# electric_schematic.net
KiCad netlist of a schematic drawn in EAGLE
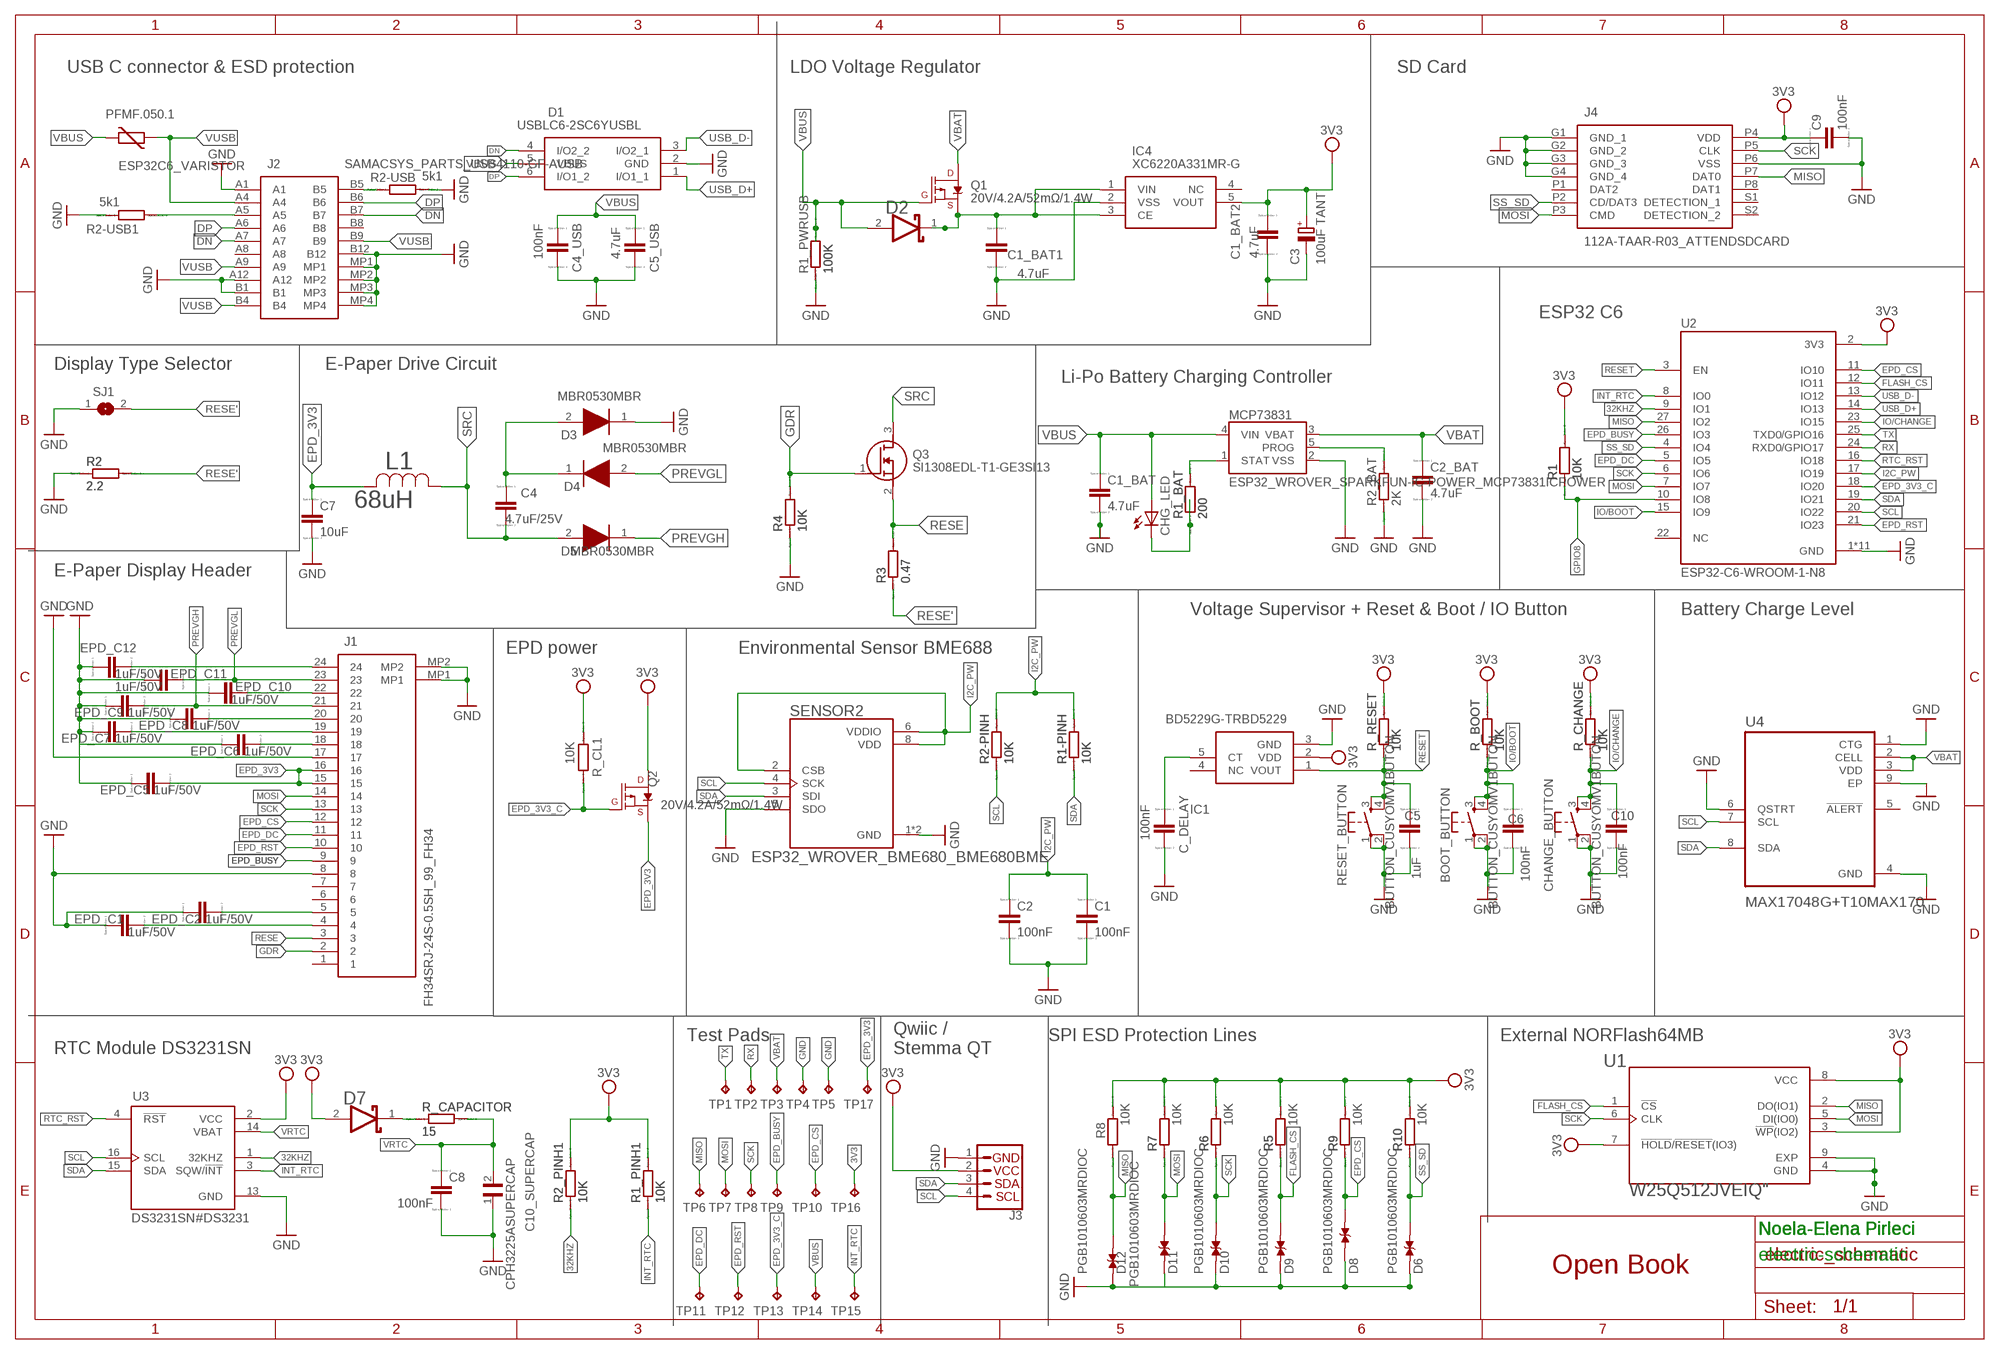
[diagram p0: schematic, sheet 1]

(export (version "E")
  (design (tool "Eeschema 10.0.6"))
  (components
    (comp (ref "BOOT_BUTTON")
      (value "BUTTON_CUSYOMV1BUTON")
      (footprint "eagle-import:MYBUTTON")
      (libsource (lib "eagle-import") (part "BUTTON_CUSYOMV1BUTON"))
    )
    (comp (ref "C1")
      (value "100nF")
      (footprint "eagle-import:ESP32_WROVER_EAGLE-LTSPICE_C0402")
      (libsource (lib "eagle-import") (part "EAGLE-LTSPICE_C"))
    )
    (comp (ref "C1_BAT")
      (value "4.7uF")
      (footprint "eagle-import:ESP32_WROVER_EAGLE-LTSPICE_C0402")
      (libsource (lib "eagle-import") (part "ESP32_WROVER_EAGLE-LTSPICE_C"))
    )
    (comp (ref "C1_BAT1")
      (value "4.7uF")
      (footprint "eagle-import:ESP32_WROVER_EAGLE-LTSPICE_C0402")
      (libsource (lib "eagle-import") (part "ESP32_WROVER_EAGLE-LTSPICE_C"))
    )
    (comp (ref "C1_BAT2")
      (value "4.7uF")
      (footprint "eagle-import:ESP32_WROVER_EAGLE-LTSPICE_C0402")
      (libsource (lib "eagle-import") (part "ESP32_WROVER_EAGLE-LTSPICE_C"))
    )
    (comp (ref "C2")
      (value "100nF")
      (footprint "eagle-import:ESP32_WROVER_EAGLE-LTSPICE_C0402")
      (libsource (lib "eagle-import") (part "ESP32_WROVER_EAGLE-LTSPICE_C"))
    )
    (comp (ref "C2_BAT")
      (value "4.7uF")
      (footprint "eagle-import:ESP32_WROVER_EAGLE-LTSPICE_C0402")
      (libsource (lib "eagle-import") (part "ESP32_WROVER_EAGLE-LTSPICE_C"))
    )
    (comp (ref "C3")
      (value "100uF TANT")
      (footprint "eagle-import:RCL_CT3528")
      (libsource (lib "eagle-import") (part "RCL_CPOL-EU"))
    )
    (comp (ref "C4")
      (value "4.7uF/25V")
      (footprint "eagle-import:ESP32_WROVER_EAGLE-LTSPICE_C0402")
      (libsource (lib "eagle-import") (part "EAGLE-LTSPICE_C"))
    )
    (comp (ref "C4_USB")
      (value "100nF")
      (footprint "eagle-import:ESP32_WROVER_EAGLE-LTSPICE_C0402")
      (libsource (lib "eagle-import") (part "EAGLE-LTSPICE_C"))
    )
    (comp (ref "C5")
      (value "1uF")
      (footprint "eagle-import:ESP32_WROVER_EAGLE-LTSPICE_C0402")
      (libsource (lib "eagle-import") (part "ESP32_WROVER_EAGLE-LTSPICE_C"))
    )
    (comp (ref "C5_USB")
      (value "4.7uF")
      (footprint "eagle-import:ESP32_WROVER_EAGLE-LTSPICE_C0402")
      (libsource (lib "eagle-import") (part "EAGLE-LTSPICE_C"))
    )
    (comp (ref "C6")
      (value "100nF")
      (footprint "eagle-import:ESP32_WROVER_EAGLE-LTSPICE_C0402")
      (libsource (lib "eagle-import") (part "ESP32_WROVER_EAGLE-LTSPICE_C"))
    )
    (comp (ref "C7")
      (value "10uF")
      (footprint "eagle-import:ESP32_WROVER_EAGLE-LTSPICE_C0402")
      (libsource (lib "eagle-import") (part "ESP32_WROVER_EAGLE-LTSPICE_C"))
    )
    (comp (ref "C8")
      (value "100nF")
      (footprint "eagle-import:ESP32_WROVER_EAGLE-LTSPICE_C0402")
      (libsource (lib "eagle-import") (part "ESP32_WROVER_EAGLE-LTSPICE_C"))
    )
    (comp (ref "C9")
      (value "100nF")
      (footprint "eagle-import:ESP32_WROVER_EAGLE-LTSPICE_C0402")
      (libsource (lib "eagle-import") (part "EAGLE-LTSPICE_C"))
    )
    (comp (ref "C10")
      (value "100nF")
      (footprint "eagle-import:ESP32_WROVER_EAGLE-LTSPICE_C0402")
      (libsource (lib "eagle-import") (part "ESP32_WROVER_EAGLE-LTSPICE_C"))
    )
    (comp (ref "C10_SUPERCAP")
      (value "CPH3225ASUPERCAP")
      (footprint "eagle-import:CAPCP3225X100N")
      (libsource (lib "eagle-import") (part "CPH3225ASUPERCAP"))
    )
    (comp (ref "CHANGE_BUTTON")
      (value "BUTTON_CUSYOMV1BUTON")
      (footprint "eagle-import:MYBUTTON")
      (libsource (lib "eagle-import") (part "BUTTON_CUSYOMV1BUTON"))
    )
    (comp (ref "CHG_LED")
      (value "ADAFRUIT_LED")
      (footprint "eagle-import:ADAFRUIT_CHIP-LED0603")
      (libsource (lib "eagle-import") (part "ADAFRUIT_LED"))
    )
    (comp (ref "C_DELAY")
      (value "100nF")
      (footprint "eagle-import:ESP32_WROVER_EAGLE-LTSPICE_C0402")
      (libsource (lib "eagle-import") (part "EAGLE-LTSPICE_C"))
    )
    (comp (ref "D1")
      (value "USBLC6-2SC6YUSBL")
      (footprint "eagle-import:SOT95P280X145-6N")
      (libsource (lib "eagle-import") (part "USBLC6-2SC6YUSBL"))
    )
    (comp (ref "D2")
      (value "ESP32_WROVER_AVX---SD0805S020S1R0_AVX_SD0805S020S1R0_0_0")
      (footprint "eagle-import:ESP32_WROVER_AVX---SD0805S020S1R0_AVX_SD0805S020S1R0_0")
      (libsource (lib "eagle-import") (part "ESP32_WROVER_AVX---SD0805S020S1R0_AVX_SD0805S020S1R0_0_0"))
    )
    (comp (ref "D3")
      (value "MBR0530MBR")
      (footprint "eagle-import:SOD3716X135N")
      (libsource (lib "eagle-import") (part "MBR0530MBR"))
    )
    (comp (ref "D4")
      (value "MBR0530MBR")
      (footprint "eagle-import:SOD3716X135N")
      (libsource (lib "eagle-import") (part "MBR0530MBR"))
    )
    (comp (ref "D5")
      (value "MBR0530MBR")
      (footprint "eagle-import:SOD3716X135N")
      (libsource (lib "eagle-import") (part "MBR0530MBR"))
    )
    (comp (ref "D6")
      (value "PGB1010603MRDIOC")
      (footprint "eagle-import:DIOC1608X36N")
      (libsource (lib "eagle-import") (part "PGB1010603MRDIOC"))
    )
    (comp (ref "D7")
      (value "ESP32_WROVER_AVX---SD0805S020S1R0_AVX_SD0805S020S1R0_0_0")
      (footprint "eagle-import:ESP32_WROVER_AVX---SD0805S020S1R0_AVX_SD0805S020S1R0_0")
      (libsource (lib "eagle-import") (part "ESP32_WROVER_AVX---SD0805S020S1R0_AVX_SD0805S020S1R0_0_0"))
    )
    (comp (ref "D8")
      (value "PGB1010603MRDIOC")
      (footprint "eagle-import:DIOC1608X36N")
      (libsource (lib "eagle-import") (part "PGB1010603MRDIOC"))
    )
    (comp (ref "D9")
      (value "PGB1010603MRDIOC")
      (footprint "eagle-import:DIOC1608X36N")
      (libsource (lib "eagle-import") (part "PGB1010603MRDIOC"))
    )
    (comp (ref "D10")
      (value "PGB1010603MRDIOC")
      (footprint "eagle-import:DIOC1608X36N")
      (libsource (lib "eagle-import") (part "PGB1010603MRDIOC"))
    )
    (comp (ref "D11")
      (value "PGB1010603MRDIOC")
      (footprint "eagle-import:DIOC1608X36N")
      (libsource (lib "eagle-import") (part "PGB1010603MRDIOC"))
    )
    (comp (ref "D12")
      (value "PGB1010603MRDIOC")
      (footprint "eagle-import:DIOC1608X36N")
      (libsource (lib "eagle-import") (part "PGB1010603MRDIOC"))
    )
    (comp (ref "EPD_C1")
      (value "1uF/50V")
      (footprint "eagle-import:ESP32_WROVER_EAGLE-LTSPICE_C0402")
      (libsource (lib "eagle-import") (part "ESP32_WROVER_EAGLE-LTSPICE_C"))
    )
    (comp (ref "EPD_C2")
      (value "1uF/50V")
      (footprint "eagle-import:ESP32_WROVER_EAGLE-LTSPICE_C0402")
      (libsource (lib "eagle-import") (part "ESP32_WROVER_EAGLE-LTSPICE_C"))
    )
    (comp (ref "EPD_C5")
      (value "1uF/50V")
      (footprint "eagle-import:ESP32_WROVER_EAGLE-LTSPICE_C0402")
      (libsource (lib "eagle-import") (part "ESP32_WROVER_EAGLE-LTSPICE_C"))
    )
    (comp (ref "EPD_C6")
      (value "1uF/50V")
      (footprint "eagle-import:ESP32_WROVER_EAGLE-LTSPICE_C0402")
      (libsource (lib "eagle-import") (part "ESP32_WROVER_EAGLE-LTSPICE_C"))
    )
    (comp (ref "EPD_C7")
      (value "1uF/50V")
      (footprint "eagle-import:ESP32_WROVER_EAGLE-LTSPICE_C0402")
      (libsource (lib "eagle-import") (part "ESP32_WROVER_EAGLE-LTSPICE_C"))
    )
    (comp (ref "EPD_C8")
      (value "1uF/50V")
      (footprint "eagle-import:ESP32_WROVER_EAGLE-LTSPICE_C0402")
      (libsource (lib "eagle-import") (part "ESP32_WROVER_EAGLE-LTSPICE_C"))
    )
    (comp (ref "EPD_C9")
      (value "1uF/50V")
      (footprint "eagle-import:ESP32_WROVER_EAGLE-LTSPICE_C0402")
      (libsource (lib "eagle-import") (part "ESP32_WROVER_EAGLE-LTSPICE_C"))
    )
    (comp (ref "EPD_C10")
      (value "1uF/50V")
      (footprint "eagle-import:ESP32_WROVER_EAGLE-LTSPICE_C0402")
      (libsource (lib "eagle-import") (part "ESP32_WROVER_EAGLE-LTSPICE_C"))
    )
    (comp (ref "EPD_C11")
      (value "1uF/50V")
      (footprint "eagle-import:ESP32_WROVER_EAGLE-LTSPICE_C0402")
      (libsource (lib "eagle-import") (part "ESP32_WROVER_EAGLE-LTSPICE_C"))
    )
    (comp (ref "EPD_C12")
      (value "1uF/50V")
      (footprint "eagle-import:ESP32_WROVER_EAGLE-LTSPICE_C0402")
      (libsource (lib "eagle-import") (part "ESP32_WROVER_EAGLE-LTSPICE_C"))
    )
    (comp (ref "IC1")
      (value "BD5229G-TRBD5229")
      (footprint "eagle-import:SOT95P280X125-5N")
      (libsource (lib "eagle-import") (part "BD5229G-TRBD5229"))
    )
    (comp (ref "IC4")
      (value "XC6220A331MR-G")
      (footprint "eagle-import:SOT95P280X120-5N")
      (fields (field (name "MOUSER_PART_NUMBER") "865-XC6220A331MR-G"))
      (libsource (lib "eagle-import") (part "XC6220A331MR-G"))
    )
    (comp (ref "J1")
      (value "FH34SRJ-24S-0.5SH_99_FH34")
      (footprint "eagle-import:FH34SRJ24S05SH99")
      (libsource (lib "eagle-import") (part "FH34SRJ-24S-0.5SH_99_FH34"))
    )
    (comp (ref "J2")
      (value "SAMACSYS_PARTS_USB4110-GF-AUSB")
      (footprint "eagle-import:SAMACSYS_PARTS_USB4110GFA")
      (libsource (lib "eagle-import") (part "SAMACSYS_PARTS_USB4110-GF-AUSB"))
    )
    (comp (ref "J3")
      (value "QWIIC_RIGHT_ANGLE")
      (footprint "eagle-import:JST04_1MM_RA")
      (libsource (lib "eagle-import") (part "QWIIC_CONNECTOR"))
    )
    (comp (ref "J4")
      (value "112A-TAAR-R03_ATTENDSDCARD")
      (footprint "eagle-import:112ATAARR03ATTEND")
      (libsource (lib "eagle-import") (part "112A-TAAR-R03_ATTENDSDCARD"))
    )
    (comp (ref "L1")
      (value "68uH")
      (footprint "eagle-import:IND_4828-WE-TPC_WRE")
      (libsource (lib "eagle-import") (part "744043680"))
    )
    (comp (ref "MCP73831")
      (value "ESP32_WROVER_SPARKFUN-IC-POWER_MCP73831ICPOWER")
      (footprint "eagle-import:ESP32_WROVER_SPARKFUN-IC-POWER_SOT23-5")
      (libsource (lib "eagle-import") (part "ESP32_WROVER_SPARKFUN-IC-POWER_MCP73831ICPOWER"))
    )
    (comp (ref "PFMF.050.1")
      (value "ESP32C6_VARISTOR")
      (footprint "eagle-import:ESP32C6_VARISTOR_CT_CN1812")
      (libsource (lib "eagle-import") (part "ESP32C6_VARISTOR"))
    )
    (comp (ref "Q1")
      (value "20V/4.2A/52mΩ/1.4W")
      (footprint "eagle-import:ESP32_WROVER_SPARKFUN-DISCRETESEMI_SOT23-3")
      (libsource (lib "eagle-import") (part "ESP32_WROVER_SPARKFUN-DISCRETESEMI_MOSFET_PCH"))
    )
    (comp (ref "Q2")
      (value "20V/4.2A/52mΩ/1.4W")
      (footprint "eagle-import:ESP32_WROVER_SPARKFUN-DISCRETESEMI_SOT23-3")
      (libsource (lib "eagle-import") (part "ESP32_WROVER_SPARKFUN-DISCRETESEMI_MOSFET_PCH"))
    )
    (comp (ref "Q3")
      (value "SI1308EDL-T1-GE3SI13")
      (footprint "eagle-import:SOT65P210X110-3N")
      (libsource (lib "eagle-import") (part "SI1308EDL-T1-GE3SI13"))
    )
    (comp (ref "R1")
      (value "10K")
      (footprint "eagle-import:ESP32_WROVER_EAGLE-LTSPICE_R0402")
      (libsource (lib "eagle-import") (part "ESP32_WROVER_EAGLE-LTSPICE_R"))
    )
    (comp (ref "R1-PINH")
      (value "10K")
      (footprint "eagle-import:ESP32_WROVER_EAGLE-LTSPICE_R0402")
      (libsource (lib "eagle-import") (part "ESP32_WROVER_EAGLE-LTSPICE_R"))
    )
    (comp (ref "R1_BAT")
      (value "200")
      (footprint "eagle-import:ESP32_WROVER_EAGLE-LTSPICE_R0402")
      (libsource (lib "eagle-import") (part "ESP32_WROVER_EAGLE-LTSPICE_R"))
    )
    (comp (ref "R1_PINH1")
      (value "10K")
      (footprint "eagle-import:ESP32_WROVER_EAGLE-LTSPICE_R0402")
      (libsource (lib "eagle-import") (part "ESP32_WROVER_EAGLE-LTSPICE_R"))
    )
    (comp (ref "R1_PWRUSB")
      (value "100K")
      (footprint "eagle-import:ESP32_WROVER_EAGLE-LTSPICE_R0402")
      (libsource (lib "eagle-import") (part "ESP32_WROVER_EAGLE-LTSPICE_R"))
    )
    (comp (ref "R2")
      (value "2.2")
      (footprint "eagle-import:ESP32_WROVER_EAGLE-LTSPICE_R0402")
      (libsource (lib "eagle-import") (part "ESP32_WROVER_EAGLE-LTSPICE_R"))
    )
    (comp (ref "R2-PINH")
      (value "10K")
      (footprint "eagle-import:ESP32_WROVER_EAGLE-LTSPICE_R0402")
      (libsource (lib "eagle-import") (part "ESP32_WROVER_EAGLE-LTSPICE_R"))
    )
    (comp (ref "R2-USB")
      (value "5k1")
      (footprint "eagle-import:ESP32_WROVER_EAGLE-LTSPICE_R0402")
      (libsource (lib "eagle-import") (part "ESP32_WROVER_EAGLE-LTSPICE_R"))
    )
    (comp (ref "R2-USB1")
      (value "5k1")
      (footprint "eagle-import:ESP32_WROVER_EAGLE-LTSPICE_R0402")
      (libsource (lib "eagle-import") (part "ESP32_WROVER_EAGLE-LTSPICE_R"))
    )
    (comp (ref "R2_BAT")
      (value "2K")
      (footprint "eagle-import:ESP32_WROVER_EAGLE-LTSPICE_R0402")
      (libsource (lib "eagle-import") (part "ESP32_WROVER_EAGLE-LTSPICE_R"))
    )
    (comp (ref "R2_PINH1")
      (value "10K")
      (footprint "eagle-import:ESP32_WROVER_EAGLE-LTSPICE_R0402")
      (libsource (lib "eagle-import") (part "ESP32_WROVER_EAGLE-LTSPICE_R"))
    )
    (comp (ref "R3")
      (value "0.47")
      (footprint "eagle-import:ESP32_WROVER_EAGLE-LTSPICE_R0402")
      (libsource (lib "eagle-import") (part "ESP32_WROVER_EAGLE-LTSPICE_R"))
    )
    (comp (ref "R4")
      (value "10K")
      (footprint "eagle-import:ESP32_WROVER_EAGLE-LTSPICE_R0402")
      (libsource (lib "eagle-import") (part "ESP32_WROVER_EAGLE-LTSPICE_R"))
    )
    (comp (ref "R5")
      (value "10K")
      (footprint "eagle-import:ESP32_WROVER_EAGLE-LTSPICE_R0402")
      (libsource (lib "eagle-import") (part "ESP32_WROVER_EAGLE-LTSPICE_R"))
    )
    (comp (ref "R6")
      (value "10K")
      (footprint "eagle-import:ESP32_WROVER_EAGLE-LTSPICE_R0402")
      (libsource (lib "eagle-import") (part "ESP32_WROVER_EAGLE-LTSPICE_R"))
    )
    (comp (ref "R7")
      (value "10K")
      (footprint "eagle-import:ESP32_WROVER_EAGLE-LTSPICE_R0402")
      (libsource (lib "eagle-import") (part "ESP32_WROVER_EAGLE-LTSPICE_R"))
    )
    (comp (ref "R8")
      (value "10K")
      (footprint "eagle-import:ESP32_WROVER_EAGLE-LTSPICE_R0402")
      (libsource (lib "eagle-import") (part "ESP32_WROVER_EAGLE-LTSPICE_R"))
    )
    (comp (ref "R9")
      (value "10K")
      (footprint "eagle-import:ESP32_WROVER_EAGLE-LTSPICE_R0402")
      (libsource (lib "eagle-import") (part "ESP32_WROVER_EAGLE-LTSPICE_R"))
    )
    (comp (ref "R10")
      (value "10K")
      (footprint "eagle-import:ESP32_WROVER_EAGLE-LTSPICE_R0402")
      (libsource (lib "eagle-import") (part "ESP32_WROVER_EAGLE-LTSPICE_R"))
    )
    (comp (ref "RESET_BUTTON")
      (value "BUTTON_CUSYOMV1BUTON")
      (footprint "eagle-import:MYBUTTON")
      (libsource (lib "eagle-import") (part "BUTTON_CUSYOMV1BUTON"))
    )
    (comp (ref "R_BOOT")
      (value "10K")
      (footprint "eagle-import:ESP32_WROVER_EAGLE-LTSPICE_R0402")
      (libsource (lib "eagle-import") (part "ESP32_WROVER_EAGLE-LTSPICE_R"))
    )
    (comp (ref "R_CAPACITOR")
      (value "15")
      (footprint "eagle-import:ESP32_WROVER_EAGLE-LTSPICE_R0402")
      (libsource (lib "eagle-import") (part "ESP32_WROVER_EAGLE-LTSPICE_R"))
    )
    (comp (ref "R_CHANGE")
      (value "10K")
      (footprint "eagle-import:ESP32_WROVER_EAGLE-LTSPICE_R0402")
      (libsource (lib "eagle-import") (part "ESP32_WROVER_EAGLE-LTSPICE_R"))
    )
    (comp (ref "R_CL1")
      (value "10K")
      (footprint "eagle-import:ESP32_WROVER_EAGLE-LTSPICE_R0402")
      (libsource (lib "eagle-import") (part "ESP32_WROVER_EAGLE-LTSPICE_R"))
    )
    (comp (ref "R_RESET")
      (value "10K")
      (footprint "eagle-import:ESP32_WROVER_EAGLE-LTSPICE_R0402")
      (libsource (lib "eagle-import") (part "ESP32_WROVER_EAGLE-LTSPICE_R"))
    )
    (comp (ref "SENSOR2")
      (value "ESP32_WROVER_BME680_BME680BME")
      (footprint "eagle-import:ESP32_WROVER_BME680_PSON80P300X300X100-8N")
      (libsource (lib "eagle-import") (part "ESP32_WROVER_BME680_BME680BME"))
    )
    (comp (ref "SJ1") (value "SJ") (footprint "eagle-import:SJ") (libsource (lib "eagle-import") (part "SJ")))
    (comp (ref "TP1")
      (value "TPMODEL")
      (footprint "eagle-import:TP20R")
      (libsource (lib "eagle-import") (part "TPMODEL"))
    )
    (comp (ref "TP2")
      (value "TPMODEL")
      (footprint "eagle-import:TP20R")
      (libsource (lib "eagle-import") (part "TPMODEL"))
    )
    (comp (ref "TP3")
      (value "TPMODEL")
      (footprint "eagle-import:TP20R")
      (libsource (lib "eagle-import") (part "TPMODEL"))
    )
    (comp (ref "TP4")
      (value "TPTP20R")
      (footprint "eagle-import:TP20R")
      (libsource (lib "eagle-import") (part "TPMODEL"))
    )
    (comp (ref "TP5")
      (value "TPTP20R")
      (footprint "eagle-import:TP20R")
      (libsource (lib "eagle-import") (part "TPMODEL"))
    )
    (comp (ref "TP6")
      (value "TPTP20R")
      (footprint "eagle-import:TP20R")
      (libsource (lib "eagle-import") (part "TPMODEL"))
    )
    (comp (ref "TP7")
      (value "TPMODEL")
      (footprint "eagle-import:TP20R")
      (libsource (lib "eagle-import") (part "TPMODEL"))
    )
    (comp (ref "TP8")
      (value "TPMODEL")
      (footprint "eagle-import:TP20R")
      (libsource (lib "eagle-import") (part "TPMODEL"))
    )
    (comp (ref "TP9")
      (value "TPMODEL")
      (footprint "eagle-import:TP20R")
      (libsource (lib "eagle-import") (part "TPMODEL"))
    )
    (comp (ref "TP10")
      (value "TPMODEL")
      (footprint "eagle-import:TP20R")
      (libsource (lib "eagle-import") (part "TPMODEL"))
    )
    (comp (ref "TP11")
      (value "TPTP20R")
      (footprint "eagle-import:TP20R")
      (libsource (lib "eagle-import") (part "TPMODEL"))
    )
    (comp (ref "TP12")
      (value "TPMODEL")
      (footprint "eagle-import:TP20R")
      (libsource (lib "eagle-import") (part "TPMODEL"))
    )
    (comp (ref "TP13")
      (value "TPMODEL")
      (footprint "eagle-import:TP20R")
      (libsource (lib "eagle-import") (part "TPMODEL"))
    )
    (comp (ref "TP14")
      (value "TPTP20R")
      (footprint "eagle-import:TP20R")
      (libsource (lib "eagle-import") (part "TPMODEL"))
    )
    (comp (ref "TP15")
      (value "TPMODEL")
      (footprint "eagle-import:TP20R")
      (libsource (lib "eagle-import") (part "TPMODEL"))
    )
    (comp (ref "TP16")
      (value "TPMODEL")
      (footprint "eagle-import:TP20R")
      (libsource (lib "eagle-import") (part "TPMODEL"))
    )
    (comp (ref "TP17")
      (value "TPMODEL")
      (footprint "eagle-import:TP20R")
      (libsource (lib "eagle-import") (part "TPMODEL"))
    )
    (comp (ref "U1")
      (value "W25Q512JVEIQ\"")
      (footprint "eagle-import:SON127P600X800X80-9N")
      (libsource (lib "eagle-import") (part "W25Q512JVEIQ{dblquote}"))
    )
    (comp (ref "U2")
      (value "ESP32-C6-WROOM-1-N8")
      (footprint "eagle-import:XCVR_ESP32-C6-WROOM-1-N8")
      (libsource (lib "eagle-import") (part "ESP32-C6-WROOM-1-N8ESP32"))
    )
    (comp (ref "U3")
      (value "DS3231SN#DS3231")
      (footprint "eagle-import:SOIC127P1032X265-16N")
      (libsource (lib "eagle-import") (part "DS3231SN#DS3231"))
    )
    (comp (ref "U4")
      (value "MAX17048G+T10MAX170")
      (footprint "eagle-import:SON50P200X200X80-9N")
      (libsource (lib "eagle-import") (part "MAX17048G+T10MAX170"))
    )
  )
  (nets
    (net (code "1") (name "3V3") (class "Default")
      (node (ref "C1_BAT2") (pin "1") (pinfunction "1_1") (pintype "passive"))
      (node (ref "C3") (pin "+") (pinfunction "+_+") (pintype "passive"))
      (node (ref "C9") (pin "1") (pinfunction "1_1") (pintype "passive"))
      (node (ref "D7") (pin "2") (pinfunction "ANODE_2") (pintype "bidirectional"))
      (node (ref "IC1") (pin "2") (pinfunction "VDD_2") (pintype "bidirectional"))
      (node (ref "IC4") (pin "5") (pinfunction "VOUT_5") (pintype "bidirectional"))
      (node (ref "J3") (pin "2") (pinfunction "2_2") (pintype "power_in"))
      (node (ref "J4") (pin "P4") (pinfunction "VDD_P4") (pintype "bidirectional"))
      (node (ref "Q2") (pin "3") (pinfunction "D_3") (pintype "bidirectional"))
      (node (ref "R1") (pin "2") (pinfunction "2_2") (pintype "passive"))
      (node (ref "R10") (pin "2") (pinfunction "2_2") (pintype "passive"))
      (node (ref "R1_PINH1") (pin "2") (pinfunction "2_2") (pintype "passive"))
      (node (ref "R2_PINH1") (pin "2") (pinfunction "2_2") (pintype "passive"))
      (node (ref "R5") (pin "2") (pinfunction "2_2") (pintype "passive"))
      (node (ref "R6") (pin "2") (pinfunction "2_2") (pintype "passive"))
      (node (ref "R7") (pin "2") (pinfunction "2_2") (pintype "passive"))
      (node (ref "R8") (pin "2") (pinfunction "2_2") (pintype "passive"))
      (node (ref "R9") (pin "2") (pinfunction "2_2") (pintype "passive"))
      (node (ref "R_BOOT") (pin "2") (pinfunction "2_2") (pintype "passive"))
      (node (ref "R_CHANGE") (pin "2") (pinfunction "2_2") (pintype "passive"))
      (node (ref "R_CL1") (pin "2") (pinfunction "2_2") (pintype "passive"))
      (node (ref "R_RESET") (pin "2") (pinfunction "2_2") (pintype "passive"))
      (node (ref "TP16") (pin "TP") (pinfunction "TP_TP") (pintype "input"))
      (node (ref "U1") (pin "3") (pinfunction "~{WP}(IO2)_3") (pintype "bidirectional"))
      (node (ref "U1") (pin "7") (pinfunction "~{HOLD}/~{RESET}(IO3)_7") (pintype "bidirectional"))
      (node (ref "U1") (pin "8") (pinfunction "VCC_8") (pintype "power_in"))
      (node (ref "U2") (pin "2") (pinfunction "3V3_2") (pintype "power_in"))
      (node (ref "U3") (pin "2") (pinfunction "VCC_2") (pintype "power_in"))
    )
    (net (code "2") (name "32KHZ") (class "Default")
      (node (ref "R2_PINH1") (pin "1") (pinfunction "1_1") (pintype "passive"))
      (node (ref "U2") (pin "9") (pinfunction "IO1_9") (pintype "bidirectional"))
      (node (ref "U3") (pin "1") (pinfunction "32KHZ_1") (pintype "output"))
    )
    (net (code "3") (name "DN") (class "Default")
      (node (ref "D1") (pin "4") (pinfunction "I/O2_2_4") (pintype "bidirectional"))
      (node (ref "J2") (pin "A7") (pinfunction "A7_A7") (pintype "bidirectional"))
      (node (ref "J2") (pin "B7") (pinfunction "B7_B7") (pintype "bidirectional"))
    )
    (net (code "4") (name "DP") (class "Default")
      (node (ref "D1") (pin "6") (pinfunction "I/O1_2_6") (pintype "bidirectional"))
      (node (ref "J2") (pin "A6") (pinfunction "A6_A6") (pintype "bidirectional"))
      (node (ref "J2") (pin "B6") (pinfunction "B6_B6") (pintype "bidirectional"))
    )
    (net (code "5") (name "EPD_3V3") (class "Default")
      (node (ref "C7") (pin "1") (pinfunction "1_1") (pintype "passive"))
      (node (ref "EPD_C5") (pin "2") (pinfunction "2_2") (pintype "passive"))
      (node (ref "J1") (pin "15") (pinfunction "15_15") (pintype "bidirectional"))
      (node (ref "J1") (pin "16") (pinfunction "16_16") (pintype "bidirectional"))
      (node (ref "L1") (pin "2") (pinfunction "2_2") (pintype "passive"))
      (node (ref "Q2") (pin "2") (pinfunction "S_2") (pintype "bidirectional"))
      (node (ref "TP17") (pin "TP") (pinfunction "TP_TP") (pintype "input"))
    )
    (net (code "6") (name "EPD_3V3_C") (class "Default")
      (node (ref "Q2") (pin "1") (pinfunction "G_1") (pintype "bidirectional"))
      (node (ref "R_CL1") (pin "1") (pinfunction "1_1") (pintype "passive"))
      (node (ref "TP13") (pin "TP") (pinfunction "TP_TP") (pintype "input"))
      (node (ref "U2") (pin "18") (pinfunction "IO20_18") (pintype "bidirectional"))
    )
    (net (code "7") (name "EPD_BUSY") (class "Default")
      (node (ref "J1") (pin "9") (pinfunction "9_9") (pintype "bidirectional"))
      (node (ref "TP9") (pin "TP") (pinfunction "TP_TP") (pintype "input"))
      (node (ref "U2") (pin "26") (pinfunction "IO3_26") (pintype "bidirectional"))
    )
    (net (code "8") (name "EPD_CS") (class "Default")
      (node (ref "D8") (pin "2") (pinfunction "2_2") (pintype "passive"))
      (node (ref "J1") (pin "12") (pinfunction "12_12") (pintype "bidirectional"))
      (node (ref "R9") (pin "1") (pinfunction "1_1") (pintype "passive"))
      (node (ref "TP10") (pin "TP") (pinfunction "TP_TP") (pintype "input"))
      (node (ref "U2") (pin "11") (pinfunction "IO10_11") (pintype "bidirectional"))
    )
    (net (code "9") (name "EPD_DC") (class "Default")
      (node (ref "J1") (pin "11") (pinfunction "11_11") (pintype "bidirectional"))
      (node (ref "TP11") (pin "TP") (pinfunction "TP_TP") (pintype "input"))
      (node (ref "U2") (pin "5") (pinfunction "IO5_5") (pintype "bidirectional"))
    )
    (net (code "10") (name "EPD_RST") (class "Default")
      (node (ref "J1") (pin "10") (pinfunction "10_10") (pintype "bidirectional"))
      (node (ref "TP12") (pin "TP") (pinfunction "TP_TP") (pintype "input"))
      (node (ref "U2") (pin "21") (pinfunction "IO23_21") (pintype "bidirectional"))
    )
    (net (code "11") (name "FLASH_CS") (class "Default")
      (node (ref "D9") (pin "2") (pinfunction "2_2") (pintype "passive"))
      (node (ref "R5") (pin "1") (pinfunction "1_1") (pintype "passive"))
      (node (ref "U1") (pin "1") (pinfunction "~{CS}_1") (pintype "input"))
      (node (ref "U2") (pin "12") (pinfunction "IO11_12") (pintype "bidirectional"))
    )
    (net (code "12") (name "GDR") (class "Default")
      (node (ref "J1") (pin "2") (pinfunction "2_2") (pintype "bidirectional"))
      (node (ref "Q3") (pin "1") (pinfunction "G_1") (pintype "bidirectional"))
      (node (ref "R4") (pin "2") (pinfunction "2_2") (pintype "passive"))
    )
    (net (code "13") (name "GND") (class "Default")
      (node (ref "BOOT_BUTTON") (pin "1") (pinfunction "1_1") (pintype "passive"))
      (node (ref "BOOT_BUTTON") (pin "2") (pinfunction "2_2") (pintype "passive"))
      (node (ref "C1") (pin "2") (pinfunction "2_2") (pintype "passive"))
      (node (ref "C10") (pin "2") (pinfunction "2_2") (pintype "passive"))
      (node (ref "C10_SUPERCAP") (pin "1") (pinfunction "1_1") (pintype "passive"))
      (node (ref "C1_BAT") (pin "2") (pinfunction "2_2") (pintype "passive"))
      (node (ref "C1_BAT1") (pin "2") (pinfunction "2_2") (pintype "passive"))
      (node (ref "C1_BAT2") (pin "2") (pinfunction "2_2") (pintype "passive"))
      (node (ref "C2") (pin "2") (pinfunction "2_2") (pintype "passive"))
      (node (ref "C2_BAT") (pin "2") (pinfunction "2_2") (pintype "passive"))
      (node (ref "C3") (pin "-") (pinfunction "-_-") (pintype "passive"))
      (node (ref "C4_USB") (pin "2") (pinfunction "2_2") (pintype "passive"))
      (node (ref "C5") (pin "2") (pinfunction "2_2") (pintype "passive"))
      (node (ref "C5_USB") (pin "2") (pinfunction "2_2") (pintype "passive"))
      (node (ref "C6") (pin "2") (pinfunction "2_2") (pintype "passive"))
      (node (ref "C7") (pin "2") (pinfunction "2_2") (pintype "passive"))
      (node (ref "C8") (pin "2") (pinfunction "2_2") (pintype "passive"))
      (node (ref "C9") (pin "2") (pinfunction "2_2") (pintype "passive"))
      (node (ref "CHANGE_BUTTON") (pin "1") (pinfunction "1_1") (pintype "passive"))
      (node (ref "CHANGE_BUTTON") (pin "2") (pinfunction "2_2") (pintype "passive"))
      (node (ref "C_DELAY") (pin "2") (pinfunction "2_2") (pintype "passive"))
      (node (ref "D1") (pin "2") (pinfunction "GND_2") (pintype "bidirectional"))
      (node (ref "D10") (pin "1") (pinfunction "1_1") (pintype "passive"))
      (node (ref "D12") (pin "1") (pinfunction "1_1") (pintype "passive"))
      (node (ref "D3") (pin "1") (pinfunction "K_1") (pintype "bidirectional"))
      (node (ref "D6") (pin "1") (pinfunction "1_1") (pintype "passive"))
      (node (ref "D8") (pin "1") (pinfunction "1_1") (pintype "passive"))
      (node (ref "D9") (pin "1") (pinfunction "1_1") (pintype "passive"))
      (node (ref "EPD_C1") (pin "1") (pinfunction "1_1") (pintype "passive"))
      (node (ref "EPD_C10") (pin "1") (pinfunction "1_1") (pintype "passive"))
      (node (ref "EPD_C11") (pin "1") (pinfunction "1_1") (pintype "passive"))
      (node (ref "EPD_C12") (pin "1") (pinfunction "1_1") (pintype "passive"))
      (node (ref "EPD_C2") (pin "1") (pinfunction "1_1") (pintype "passive"))
      (node (ref "EPD_C5") (pin "1") (pinfunction "1_1") (pintype "passive"))
      (node (ref "EPD_C6") (pin "1") (pinfunction "1_1") (pintype "passive"))
      (node (ref "EPD_C7") (pin "1") (pinfunction "1_1") (pintype "passive"))
      (node (ref "EPD_C8") (pin "1") (pinfunction "1_1") (pintype "passive"))
      (node (ref "EPD_C9") (pin "1") (pinfunction "1_1") (pintype "passive"))
      (node (ref "IC1") (pin "3") (pinfunction "GND_3") (pintype "bidirectional"))
      (node (ref "IC4") (pin "2") (pinfunction "VSS_2") (pintype "bidirectional"))
      (node (ref "J1") (pin "17") (pinfunction "17_17") (pintype "bidirectional"))
      (node (ref "J1") (pin "8") (pinfunction "8_8") (pintype "bidirectional"))
      (node (ref "J1") (pin "MP1") (pinfunction "MP1_MP1") (pintype "bidirectional"))
      (node (ref "J1") (pin "MP2") (pinfunction "MP2_MP2") (pintype "bidirectional"))
      (node (ref "J2") (pin "A1") (pinfunction "A1_A1") (pintype "bidirectional"))
      (node (ref "J2") (pin "A12") (pinfunction "A12_A12") (pintype "bidirectional"))
      (node (ref "J2") (pin "B1") (pinfunction "B1_B1") (pintype "bidirectional"))
      (node (ref "J2") (pin "B12") (pinfunction "B12_B12") (pintype "bidirectional"))
      (node (ref "J2") (pin "MP1") (pinfunction "MP1_MP1") (pintype "bidirectional"))
      (node (ref "J2") (pin "MP2") (pinfunction "MP2_MP2") (pintype "bidirectional"))
      (node (ref "J2") (pin "MP3") (pinfunction "MP3_MP3") (pintype "bidirectional"))
      (node (ref "J2") (pin "MP4") (pinfunction "MP4_MP4") (pintype "bidirectional"))
      (node (ref "J3") (pin "1") (pinfunction "1_1") (pintype "power_in"))
      (node (ref "J4") (pin "G1") (pinfunction "GND_1_G1") (pintype "bidirectional"))
      (node (ref "J4") (pin "G2") (pinfunction "GND_2_G2") (pintype "bidirectional"))
      (node (ref "J4") (pin "G3") (pinfunction "GND_3_G3") (pintype "bidirectional"))
      (node (ref "J4") (pin "G4") (pinfunction "GND_4_G4") (pintype "bidirectional"))
      (node (ref "J4") (pin "P6") (pinfunction "VSS_P6") (pintype "bidirectional"))
      (node (ref "MCP73831") (pin "2") (pinfunction "VSS_2") (pintype "power_in"))
      (node (ref "R1_PWRUSB") (pin "1") (pinfunction "1_1") (pintype "passive"))
      (node (ref "R2") (pin "1") (pinfunction "1_1") (pintype "passive"))
      (node (ref "R2-USB") (pin "2") (pinfunction "2_2") (pintype "passive"))
      (node (ref "R2-USB1") (pin "1") (pinfunction "1_1") (pintype "passive"))
      (node (ref "R2_BAT") (pin "1") (pinfunction "1_1") (pintype "passive"))
      (node (ref "R4") (pin "1") (pinfunction "1_1") (pintype "passive"))
      (node (ref "RESET_BUTTON") (pin "1") (pinfunction "1_1") (pintype "passive"))
      (node (ref "RESET_BUTTON") (pin "2") (pinfunction "2_2") (pintype "passive"))
      (node (ref "SENSOR2") (pin "1") (pinfunction "GND_1") (pintype "power_in"))
      (node (ref "SENSOR2") (pin "5") (pinfunction "SDO_5") (pintype "bidirectional"))
      (node (ref "SENSOR2") (pin "7") (pinfunction "GND_7") (pintype "power_in"))
      (node (ref "SJ1") (pin "1") (pinfunction "1_1") (pintype "passive"))
      (node (ref "TP4") (pin "TP") (pinfunction "TP_TP") (pintype "input"))
      (node (ref "TP5") (pin "TP") (pinfunction "TP_TP") (pintype "input"))
      (node (ref "U1") (pin "4") (pinfunction "GND_4") (pintype "power_in"))
      (node (ref "U1") (pin "9") (pinfunction "EXP_9") (pintype "passive"))
      (node (ref "U2") (pin "1") (pinfunction "GND_1") (pintype "power_in"))
      (node (ref "U2") (pin "28") (pinfunction "GND_28") (pintype "power_in"))
      (node (ref "U2") (pin "29_1") (pinfunction "GND_29_1") (pintype "power_in"))
      (node (ref "U2") (pin "29_2") (pinfunction "GND_29_2") (pintype "power_in"))
      (node (ref "U2") (pin "29_3") (pinfunction "GND_29_3") (pintype "power_in"))
      (node (ref "U2") (pin "29_4") (pinfunction "GND_29_4") (pintype "power_in"))
      (node (ref "U2") (pin "29_5") (pinfunction "GND_29_5") (pintype "power_in"))
      (node (ref "U2") (pin "29_6") (pinfunction "GND_29_6") (pintype "power_in"))
      (node (ref "U2") (pin "29_7") (pinfunction "GND_29_7") (pintype "power_in"))
      (node (ref "U2") (pin "29_8") (pinfunction "GND_29_8") (pintype "power_in"))
      (node (ref "U2") (pin "29_9") (pinfunction "GND_29_9") (pintype "power_in"))
      (node (ref "U3") (pin "13") (pinfunction "GND_13") (pintype "power_in"))
      (node (ref "U4") (pin "1") (pinfunction "CTG_1") (pintype "power_in"))
      (node (ref "U4") (pin "4") (pinfunction "GND_4") (pintype "power_in"))
      (node (ref "U4") (pin "6") (pinfunction "QSTRT_6") (pintype "input"))
      (node (ref "U4") (pin "9") (pinfunction "EP_9") (pintype "power_in"))
    )
    (net (code "14") (name "GPIO8") (class "Default")
      (node (ref "R1") (pin "1") (pinfunction "1_1") (pintype "passive"))
      (node (ref "U2") (pin "10") (pinfunction "IO8_10") (pintype "bidirectional"))
    )
    (net (code "15") (name "I2C_PW") (class "Default")
      (node (ref "C1") (pin "1") (pinfunction "1_1") (pintype "passive"))
      (node (ref "C2") (pin "1") (pinfunction "1_1") (pintype "passive"))
      (node (ref "R1-PINH") (pin "2") (pinfunction "2_2") (pintype "passive"))
      (node (ref "R2-PINH") (pin "2") (pinfunction "2_2") (pintype "passive"))
      (node (ref "SENSOR2") (pin "2") (pinfunction "CSB_2") (pintype "input"))
      (node (ref "SENSOR2") (pin "6") (pinfunction "VDDIO_6") (pintype "power_in"))
      (node (ref "SENSOR2") (pin "8") (pinfunction "VDD_8") (pintype "power_in"))
      (node (ref "U2") (pin "17") (pinfunction "IO19_17") (pintype "bidirectional"))
    )
    (net (code "16") (name "INT_RTC") (class "Default")
      (node (ref "R1_PINH1") (pin "1") (pinfunction "1_1") (pintype "passive"))
      (node (ref "TP15") (pin "TP") (pinfunction "TP_TP") (pintype "input"))
      (node (ref "U2") (pin "8") (pinfunction "IO0_8") (pintype "bidirectional"))
      (node (ref "U3") (pin "3") (pinfunction "SQW/~{INT}_3") (pintype "output"))
    )
    (net (code "17") (name "IO{slash}BOOT") (class "Default")
      (node (ref "BOOT_BUTTON") (pin "3") (pinfunction "3_3") (pintype "passive"))
      (node (ref "BOOT_BUTTON") (pin "4") (pinfunction "4_4") (pintype "passive"))
      (node (ref "C6") (pin "1") (pinfunction "1_1") (pintype "passive"))
      (node (ref "R_BOOT") (pin "1") (pinfunction "1_1") (pintype "passive"))
      (node (ref "U2") (pin "15") (pinfunction "IO9_15") (pintype "bidirectional"))
    )
    (net (code "18") (name "IO{slash}CHANGE") (class "Default")
      (node (ref "C10") (pin "1") (pinfunction "1_1") (pintype "passive"))
      (node (ref "CHANGE_BUTTON") (pin "3") (pinfunction "3_3") (pintype "passive"))
      (node (ref "CHANGE_BUTTON") (pin "4") (pinfunction "4_4") (pintype "passive"))
      (node (ref "R_CHANGE") (pin "1") (pinfunction "1_1") (pintype "passive"))
      (node (ref "U2") (pin "23") (pinfunction "IO15_23") (pintype "bidirectional"))
    )
    (net (code "19") (name "MISO") (class "Default")
      (node (ref "D12") (pin "2") (pinfunction "2_2") (pintype "passive"))
      (node (ref "J4") (pin "P7") (pinfunction "DAT0_P7") (pintype "bidirectional"))
      (node (ref "R8") (pin "1") (pinfunction "1_1") (pintype "passive"))
      (node (ref "TP6") (pin "TP") (pinfunction "TP_TP") (pintype "input"))
      (node (ref "U1") (pin "2") (pinfunction "DO(IO1)_2") (pintype "bidirectional"))
      (node (ref "U2") (pin "27") (pinfunction "IO2_27") (pintype "bidirectional"))
    )
    (net (code "20") (name "MOSI") (class "Default")
      (node (ref "D11") (pin "2") (pinfunction "2_2") (pintype "passive"))
      (node (ref "J1") (pin "14") (pinfunction "14_14") (pintype "bidirectional"))
      (node (ref "J4") (pin "P3") (pinfunction "CMD_P3") (pintype "bidirectional"))
      (node (ref "R7") (pin "1") (pinfunction "1_1") (pintype "passive"))
      (node (ref "TP7") (pin "TP") (pinfunction "TP_TP") (pintype "input"))
      (node (ref "U1") (pin "5") (pinfunction "DI(IO0)_5") (pintype "bidirectional"))
      (node (ref "U2") (pin "7") (pinfunction "IO7_7") (pintype "bidirectional"))
    )
    (net (code "21") (name "Net-(CHG_LED-PadC)") (class "Default")
      (node (ref "CHG_LED") (pin "C") (pinfunction "C_C") (pintype "passive"))
      (node (ref "R1_BAT") (pin "1") (pinfunction "1_1") (pintype "passive"))
    )
    (net (code "22") (name "Net-(D2-CATHODE)") (class "Default")
      (node (ref "C1_BAT1") (pin "1") (pinfunction "1_1") (pintype "passive"))
      (node (ref "D2") (pin "1") (pinfunction "CATHODE_1") (pintype "bidirectional"))
      (node (ref "IC4") (pin "1") (pinfunction "VIN_1") (pintype "bidirectional"))
      (node (ref "IC4") (pin "3") (pinfunction "CE_3") (pintype "bidirectional"))
      (node (ref "Q1") (pin "2") (pinfunction "S_2") (pintype "bidirectional"))
    )
    (net (code "23") (name "Net-(D3-A)") (class "Default")
      (node (ref "C4") (pin "1") (pinfunction "1_1") (pintype "passive"))
      (node (ref "D3") (pin "2") (pinfunction "A_2") (pintype "bidirectional"))
      (node (ref "D4") (pin "1") (pinfunction "K_1") (pintype "bidirectional"))
    )
    (net (code "24") (name "Net-(D7-CATHODE)") (class "Default")
      (node (ref "D7") (pin "1") (pinfunction "CATHODE_1") (pintype "bidirectional"))
      (node (ref "R_CAPACITOR") (pin "1") (pinfunction "1_1") (pintype "passive"))
    )
    (net (code "25") (name "Net-(EPD_C1-Pad2)") (class "Default")
      (node (ref "EPD_C1") (pin "2") (pinfunction "2_2") (pintype "passive"))
      (node (ref "J1") (pin "4") (pinfunction "4_4") (pintype "bidirectional"))
    )
    (net (code "26") (name "Net-(EPD_C2-Pad2)") (class "Default")
      (node (ref "EPD_C2") (pin "2") (pinfunction "2_2") (pintype "passive"))
      (node (ref "J1") (pin "5") (pinfunction "5_5") (pintype "bidirectional"))
    )
    (net (code "27") (name "Net-(EPD_C6-Pad2)") (class "Default")
      (node (ref "EPD_C6") (pin "2") (pinfunction "2_2") (pintype "passive"))
      (node (ref "J1") (pin "18") (pinfunction "18_18") (pintype "bidirectional"))
    )
    (net (code "28") (name "Net-(EPD_C7-Pad2)") (class "Default")
      (node (ref "EPD_C7") (pin "2") (pinfunction "2_2") (pintype "passive"))
      (node (ref "J1") (pin "19") (pinfunction "19_19") (pintype "bidirectional"))
    )
    (net (code "29") (name "Net-(EPD_C8-Pad2)") (class "Default")
      (node (ref "EPD_C8") (pin "2") (pinfunction "2_2") (pintype "passive"))
      (node (ref "J1") (pin "20") (pinfunction "20_20") (pintype "bidirectional"))
    )
    (net (code "30") (name "Net-(EPD_C10-Pad2)") (class "Default")
      (node (ref "EPD_C10") (pin "2") (pinfunction "2_2") (pintype "passive"))
      (node (ref "J1") (pin "22") (pinfunction "22_22") (pintype "bidirectional"))
    )
    (net (code "31") (name "Net-(EPD_C12-Pad2)") (class "Default")
      (node (ref "EPD_C12") (pin "2") (pinfunction "2_2") (pintype "passive"))
      (node (ref "J1") (pin "24") (pinfunction "24_24") (pintype "bidirectional"))
    )
    (net (code "32") (name "Net-(IC1-CT)") (class "Default")
      (node (ref "C_DELAY") (pin "1") (pinfunction "1_1") (pintype "passive"))
      (node (ref "IC1") (pin "5") (pinfunction "CT_5") (pintype "bidirectional"))
    )
    (net (code "33") (name "Net-(J2-PadA5)") (class "Default")
      (node (ref "J2") (pin "A5") (pinfunction "A5_A5") (pintype "bidirectional"))
      (node (ref "R2-USB1") (pin "2") (pinfunction "2_2") (pintype "passive"))
    )
    (net (code "34") (name "Net-(J2-PadB5)") (class "Default")
      (node (ref "J2") (pin "B5") (pinfunction "B5_B5") (pintype "bidirectional"))
      (node (ref "R2-USB") (pin "1") (pinfunction "1_1") (pintype "passive"))
    )
    (net (code "35") (name "Net-(MCP73831-PROG)") (class "Default")
      (node (ref "MCP73831") (pin "5") (pinfunction "PROG_5") (pintype "input"))
      (node (ref "R2_BAT") (pin "2") (pinfunction "2_2") (pintype "passive"))
    )
    (net (code "36") (name "Net-(MCP73831-STAT)") (class "Default")
      (node (ref "MCP73831") (pin "1") (pinfunction "STAT_1") (pintype "output"))
      (node (ref "R1_BAT") (pin "2") (pinfunction "2_2") (pintype "passive"))
    )
    (net (code "37") (name "PREVGH") (class "Default")
      (node (ref "D5") (pin "1") (pinfunction "K_1") (pintype "bidirectional"))
      (node (ref "EPD_C9") (pin "2") (pinfunction "2_2") (pintype "passive"))
      (node (ref "J1") (pin "21") (pinfunction "21_21") (pintype "bidirectional"))
    )
    (net (code "38") (name "PREVGL") (class "Default")
      (node (ref "D4") (pin "2") (pinfunction "A_2") (pintype "bidirectional"))
      (node (ref "EPD_C11") (pin "2") (pinfunction "2_2") (pintype "passive"))
      (node (ref "J1") (pin "23") (pinfunction "23_23") (pintype "bidirectional"))
    )
    (net (code "39") (name "RESE") (class "Default")
      (node (ref "J1") (pin "3") (pinfunction "3_3") (pintype "bidirectional"))
      (node (ref "Q3") (pin "2") (pinfunction "S_2") (pintype "bidirectional"))
      (node (ref "R3") (pin "2") (pinfunction "2_2") (pintype "passive"))
    )
    (net (code "40") (name "RESE'") (class "Default")
      (node (ref "R2") (pin "2") (pinfunction "2_2") (pintype "passive"))
      (node (ref "R3") (pin "1") (pinfunction "1_1") (pintype "passive"))
      (node (ref "SJ1") (pin "2") (pinfunction "2_2") (pintype "passive"))
    )
    (net (code "41") (name "RESET") (class "Default")
      (node (ref "C5") (pin "1") (pinfunction "1_1") (pintype "passive"))
      (node (ref "IC1") (pin "1") (pinfunction "VOUT_1") (pintype "bidirectional"))
      (node (ref "RESET_BUTTON") (pin "3") (pinfunction "3_3") (pintype "passive"))
      (node (ref "RESET_BUTTON") (pin "4") (pinfunction "4_4") (pintype "passive"))
      (node (ref "R_RESET") (pin "1") (pinfunction "1_1") (pintype "passive"))
      (node (ref "U2") (pin "3") (pinfunction "EN_3") (pintype "input"))
    )
    (net (code "42") (name "RTC_RST") (class "Default")
      (node (ref "U2") (pin "16") (pinfunction "IO18_16") (pintype "bidirectional"))
      (node (ref "U3") (pin "4") (pinfunction "~{RST}_4") (pintype "input"))
    )
    (net (code "43") (name "RX") (class "Default")
      (node (ref "TP2") (pin "TP") (pinfunction "TP_TP") (pintype "input"))
      (node (ref "U2") (pin "24") (pinfunction "RXD0/GPIO17_24") (pintype "bidirectional"))
    )
    (net (code "44") (name "SCK") (class "Default")
      (node (ref "D10") (pin "2") (pinfunction "2_2") (pintype "passive"))
      (node (ref "J1") (pin "13") (pinfunction "13_13") (pintype "bidirectional"))
      (node (ref "J4") (pin "P5") (pinfunction "CLK_P5") (pintype "bidirectional"))
      (node (ref "R6") (pin "1") (pinfunction "1_1") (pintype "passive"))
      (node (ref "TP8") (pin "TP") (pinfunction "TP_TP") (pintype "input"))
      (node (ref "U1") (pin "6") (pinfunction "CLK_6") (pintype "input"))
      (node (ref "U2") (pin "6") (pinfunction "IO6_6") (pintype "bidirectional"))
    )
    (net (code "45") (name "SCL") (class "Default")
      (node (ref "J3") (pin "4") (pinfunction "4_4") (pintype "passive"))
      (node (ref "R2-PINH") (pin "1") (pinfunction "1_1") (pintype "passive"))
      (node (ref "SENSOR2") (pin "4") (pinfunction "SCK_4") (pintype "input"))
      (node (ref "U2") (pin "20") (pinfunction "IO22_20") (pintype "bidirectional"))
      (node (ref "U3") (pin "16") (pinfunction "SCL_16") (pintype "input"))
      (node (ref "U4") (pin "7") (pinfunction "SCL_7") (pintype "input"))
    )
    (net (code "46") (name "SDA") (class "Default")
      (node (ref "J3") (pin "3") (pinfunction "3_3") (pintype "passive"))
      (node (ref "R1-PINH") (pin "1") (pinfunction "1_1") (pintype "passive"))
      (node (ref "SENSOR2") (pin "3") (pinfunction "SDI_3") (pintype "bidirectional"))
      (node (ref "U2") (pin "19") (pinfunction "IO21_19") (pintype "bidirectional"))
      (node (ref "U3") (pin "15") (pinfunction "SDA_15") (pintype "bidirectional"))
      (node (ref "U4") (pin "8") (pinfunction "SDA_8") (pintype "bidirectional"))
    )
    (net (code "47") (name "SRC") (class "Default")
      (node (ref "C4") (pin "2") (pinfunction "2_2") (pintype "passive"))
      (node (ref "D5") (pin "2") (pinfunction "A_2") (pintype "bidirectional"))
      (node (ref "L1") (pin "1") (pinfunction "1_1") (pintype "passive"))
      (node (ref "Q3") (pin "3") (pinfunction "D_3") (pintype "bidirectional"))
    )
    (net (code "48") (name "SS_SD") (class "Default")
      (node (ref "D6") (pin "2") (pinfunction "2_2") (pintype "passive"))
      (node (ref "J4") (pin "P2") (pinfunction "CD/DAT3_P2") (pintype "bidirectional"))
      (node (ref "R10") (pin "1") (pinfunction "1_1") (pintype "passive"))
      (node (ref "U2") (pin "4") (pinfunction "IO4_4") (pintype "bidirectional"))
    )
    (net (code "49") (name "TX") (class "Default")
      (node (ref "TP1") (pin "TP") (pinfunction "TP_TP") (pintype "input"))
      (node (ref "U2") (pin "25") (pinfunction "TXD0/GPIO16_25") (pintype "bidirectional"))
    )
    (net (code "50") (name "USB_D+") (class "Default")
      (node (ref "D1") (pin "1") (pinfunction "I/O1_1_1") (pintype "bidirectional"))
      (node (ref "U2") (pin "14") (pinfunction "IO13_14") (pintype "bidirectional"))
    )
    (net (code "51") (name "USB_D-") (class "Default")
      (node (ref "D1") (pin "3") (pinfunction "I/O2_1_3") (pintype "bidirectional"))
      (node (ref "U2") (pin "13") (pinfunction "IO12_13") (pintype "bidirectional"))
    )
    (net (code "52") (name "VBAT") (class "Default")
      (node (ref "C2_BAT") (pin "1") (pinfunction "1_1") (pintype "passive"))
      (node (ref "MCP73831") (pin "3") (pinfunction "VBAT_3") (pintype "power_in"))
      (node (ref "Q1") (pin "3") (pinfunction "D_3") (pintype "bidirectional"))
      (node (ref "TP3") (pin "TP") (pinfunction "TP_TP") (pintype "input"))
      (node (ref "U4") (pin "2") (pinfunction "CELL_2") (pintype "power_in"))
      (node (ref "U4") (pin "3") (pinfunction "VDD_3") (pintype "power_in"))
    )
    (net (code "53") (name "VBUS") (class "Default")
      (node (ref "C1_BAT") (pin "1") (pinfunction "1_1") (pintype "passive"))
      (node (ref "C4_USB") (pin "1") (pinfunction "1_1") (pintype "passive"))
      (node (ref "C5_USB") (pin "1") (pinfunction "1_1") (pintype "passive"))
      (node (ref "CHG_LED") (pin "A") (pinfunction "A_A") (pintype "passive"))
      (node (ref "D1") (pin "5") (pinfunction "VBUS_5") (pintype "bidirectional"))
      (node (ref "D2") (pin "2") (pinfunction "ANODE_2") (pintype "bidirectional"))
      (node (ref "MCP73831") (pin "4") (pinfunction "VIN_4") (pintype "power_in"))
      (node (ref "PFMF.050.1") (pin "2") (pinfunction "2_2") (pintype "passive"))
      (node (ref "Q1") (pin "1") (pinfunction "G_1") (pintype "bidirectional"))
      (node (ref "R1_PWRUSB") (pin "2") (pinfunction "2_2") (pintype "passive"))
      (node (ref "TP14") (pin "TP") (pinfunction "TP_TP") (pintype "input"))
    )
    (net (code "54") (name "VRTC") (class "Default")
      (node (ref "C10_SUPERCAP") (pin "2") (pinfunction "2_2") (pintype "passive"))
      (node (ref "C8") (pin "1") (pinfunction "1_1") (pintype "passive"))
      (node (ref "R_CAPACITOR") (pin "2") (pinfunction "2_2") (pintype "passive"))
      (node (ref "U3") (pin "14") (pinfunction "VBAT_14") (pintype "power_in"))
    )
    (net (code "55") (name "VUSB") (class "Default")
      (node (ref "J2") (pin "A4") (pinfunction "A4_A4") (pintype "bidirectional"))
      (node (ref "J2") (pin "A9") (pinfunction "A9_A9") (pintype "bidirectional"))
      (node (ref "J2") (pin "B4") (pinfunction "B4_B4") (pintype "bidirectional"))
      (node (ref "J2") (pin "B9") (pinfunction "B9_B9") (pintype "bidirectional"))
      (node (ref "PFMF.050.1") (pin "1") (pinfunction "1_1") (pintype "passive"))
    )
    (net (code "56") (name "unconnected-(D11-Pad1)") (class "Default")
      (node (ref "D11") (pin "1") (pinfunction "1_1") (pintype "passive"))
    )
    (net (code "57") (name "unconnected-(IC1-NC-Pad4)") (class "Default")
      (node (ref "IC1") (pin "4") (pinfunction "NC_4") (pintype "no_connect"))
    )
    (net (code "58") (name "unconnected-(IC4-NC-Pad4)") (class "Default")
      (node (ref "IC4") (pin "4") (pinfunction "NC_4") (pintype "no_connect"))
    )
    (net (code "59") (name "unconnected-(J1-Pad1)") (class "Default")
      (node (ref "J1") (pin "1") (pinfunction "1_1") (pintype "bidirectional"))
    )
    (net (code "60") (name "unconnected-(J1-Pad6)") (class "Default")
      (node (ref "J1") (pin "6") (pinfunction "6_6") (pintype "bidirectional"))
    )
    (net (code "61") (name "unconnected-(J1-Pad7)") (class "Default")
      (node (ref "J1") (pin "7") (pinfunction "7_7") (pintype "bidirectional"))
    )
    (net (code "62") (name "unconnected-(J2-PadA8)") (class "Default")
      (node (ref "J2") (pin "A8") (pinfunction "A8_A8") (pintype "bidirectional"))
    )
    (net (code "63") (name "unconnected-(J2-PadB8)") (class "Default")
      (node (ref "J2") (pin "B8") (pinfunction "B8_B8") (pintype "bidirectional"))
    )
    (net (code "64") (name "unconnected-(J4-DAT1-PadP8)") (class "Default")
      (node (ref "J4") (pin "P8") (pinfunction "DAT1_P8") (pintype "bidirectional"))
    )
    (net (code "65") (name "unconnected-(J4-DAT2-PadP1)") (class "Default")
      (node (ref "J4") (pin "P1") (pinfunction "DAT2_P1") (pintype "bidirectional"))
    )
    (net (code "66") (name "unconnected-(J4-DETECTION_1-PadS1)") (class "Default")
      (node (ref "J4") (pin "S1") (pinfunction "DETECTION_1_S1") (pintype "bidirectional"))
    )
    (net (code "67") (name "unconnected-(J4-DETECTION_2-PadS2)") (class "Default")
      (node (ref "J4") (pin "S2") (pinfunction "DETECTION_2_S2") (pintype "bidirectional"))
    )
    (net (code "68") (name "unconnected-(U2-NC-Pad22)") (class "Default")
      (node (ref "U2") (pin "22") (pinfunction "NC_22") (pintype "no_connect"))
    )
    (net (code "69") (name "unconnected-(U4-~{ALERT}-Pad5)") (class "Default")
      (node (ref "U4") (pin "5") (pinfunction "~{ALERT}_5") (pintype "output"))
    )
  )
)
